# mcRelay.net
KiCad netlist of a schematic drawn in EAGLE
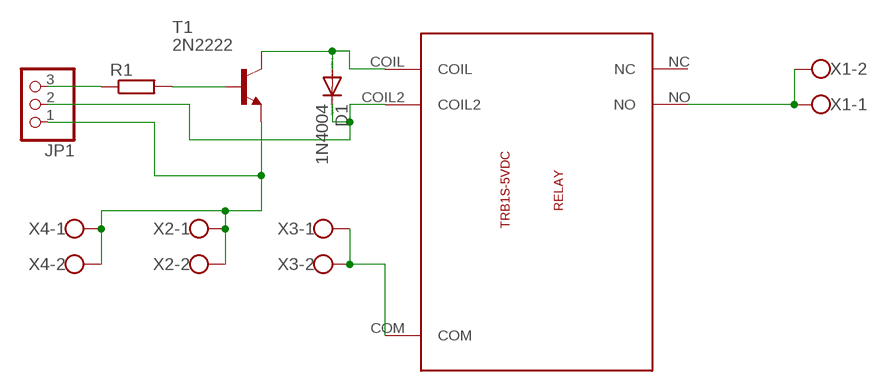
[diagram p0: schematic, sheet 1]

(export (version "E")
  (design (tool "Eeschema 10.0.6"))
  (components
    (comp (ref "D1")
      (value "1N4004")
      (footprint "eagle-import:DO41-10")
      (libsource (lib "eagle-import") (part "1N4004"))
    )
    (comp (ref "JP1")
      (value "PINHD-1X3")
      (footprint "eagle-import:1X03")
      (libsource (lib "eagle-import") (part "PINHD-1X3"))
    )
    (comp (ref "R1")
      (value "R-EU_0204/7")
      (footprint "eagle-import:0204_7")
      (libsource (lib "eagle-import") (part "R-EU_0204/7"))
    )
    (comp (ref "T1")
      (value "2N2222")
      (footprint "eagle-import:TO18")
      (libsource (lib "eagle-import") (part "2N2222"))
    )
    (comp (ref "U$1")
      (value "TRB1S-5VDC-RELAY-DEV")
      (footprint "eagle-import:TRB1S-5VDC-RELAY-PAC")
      (libsource (lib "eagle-import") (part "TRB1S-5VDC-RELAY-DEV"))
    )
    (comp (ref "X1")
      (value "W237-102")
      (footprint "eagle-import:W237-102")
      (fields (field (name "MPN") "237-102"))
      (libsource (lib "eagle-import") (part "W237-102"))
    )
    (comp (ref "X2")
      (value "W237-102")
      (footprint "eagle-import:W237-102")
      (fields (field (name "MPN") "237-102"))
      (libsource (lib "eagle-import") (part "W237-102"))
    )
    (comp (ref "X3")
      (value "W237-102")
      (footprint "eagle-import:W237-102")
      (fields (field (name "MPN") "237-102"))
      (libsource (lib "eagle-import") (part "W237-102"))
    )
    (comp (ref "X4")
      (value "W237-102")
      (footprint "eagle-import:W237-102")
      (fields (field (name "MPN") "237-102"))
      (libsource (lib "eagle-import") (part "W237-102"))
    )
  )
  (nets
    (net (code "1") (name "Net-(D1-PadC)") (class "Default")
      (node (ref "D1") (pin "C") (pinfunction "C_C") (pintype "passive"))
      (node (ref "JP1") (pin "2") (pinfunction "2_2") (pintype "passive"))
      (node (ref "U$1") (pin "COIL2") (pinfunction "COIL2_COIL2") (pintype "bidirectional"))
    )
    (net (code "2") (name "Net-(JP1-Pad3)") (class "Default")
      (node (ref "JP1") (pin "3") (pinfunction "3_3") (pintype "passive"))
      (node (ref "R1") (pin "1") (pinfunction "1_1") (pintype "passive"))
    )
    (net (code "3") (name "Net-(T1-B)") (class "Default")
      (node (ref "R1") (pin "2") (pinfunction "2_2") (pintype "passive"))
      (node (ref "T1") (pin "2") (pinfunction "B_2") (pintype "passive"))
    )
    (net (code "4") (name "Net-(T1-C)") (class "Default")
      (node (ref "D1") (pin "A") (pinfunction "A_A") (pintype "passive"))
      (node (ref "T1") (pin "3") (pinfunction "C_3") (pintype "passive"))
      (node (ref "U$1") (pin "COIL") (pinfunction "COIL_COIL") (pintype "bidirectional"))
    )
    (net (code "5") (name "Net-(T1-E)") (class "Default")
      (node (ref "JP1") (pin "1") (pinfunction "1_1") (pintype "passive"))
      (node (ref "T1") (pin "1") (pinfunction "E_1") (pintype "passive"))
      (node (ref "X2") (pin "1") (pinfunction "KL_1") (pintype "passive"))
      (node (ref "X2") (pin "2") (pinfunction "KL_2") (pintype "passive"))
      (node (ref "X4") (pin "1") (pinfunction "KL_1") (pintype "passive"))
      (node (ref "X4") (pin "2") (pinfunction "KL_2") (pintype "passive"))
    )
    (net (code "6") (name "Net-(X1A-KL)") (class "Default")
      (node (ref "U$1") (pin "NO") (pinfunction "NO_NO") (pintype "bidirectional"))
      (node (ref "X1") (pin "1") (pinfunction "KL_1") (pintype "passive"))
      (node (ref "X1") (pin "2") (pinfunction "KL_2") (pintype "passive"))
    )
    (net (code "7") (name "Net-(X3A-KL)") (class "Default")
      (node (ref "U$1") (pin "COM") (pinfunction "COM_COM") (pintype "bidirectional"))
      (node (ref "X3") (pin "1") (pinfunction "KL_1") (pintype "passive"))
      (node (ref "X3") (pin "2") (pinfunction "KL_2") (pintype "passive"))
    )
    (net (code "8") (name "unconnected-(U$1-PadNC)") (class "Default")
      (node (ref "U$1") (pin "NC") (pinfunction "NC_NC") (pintype "bidirectional"))
    )
  )
)
